# ConnectorBreakout.net
KiCad netlist of a schematic drawn in Altium Designer
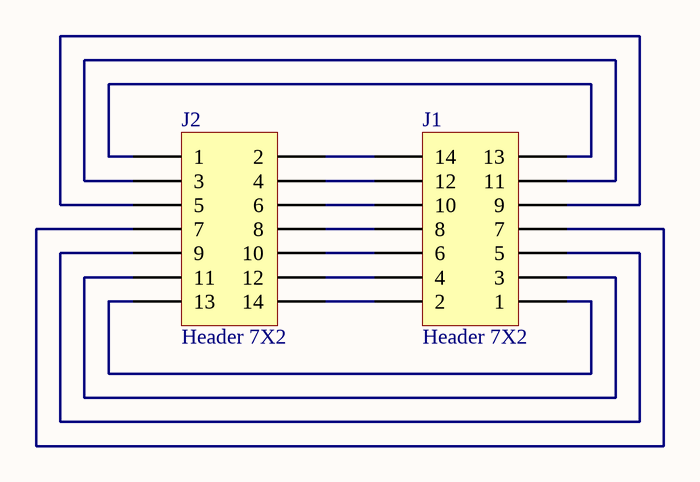
[diagram p0: ConnectorBreakout.SchDoc]

(export (version "E")
  (design (tool "Eeschema 10.0.6"))
  (components
    (comp (ref "J1")
      (value "Header 7X2")
      (footprint "HDR2X7H")
      (description "Header, 7-Pin, Dual row")
      (fields (field (name "PUBLISHER") "Altium Limited"))
      (libsource (lib "") (part "Header 7X2_1"))
    )
    (comp (ref "J2")
      (value "Header 7X2")
      (footprint "CLP-107-02-L-DH-TR")
      (description "Header, 7-Pin, Dual row")
      (fields (field (name "PUBLISHER") "Altium Limited"))
      (libsource (lib "Miscellaneous Connectors") (part "Header 7X2"))
    )
  )
  (nets
    (net (code "1") (name "Net-(J1-Pad1)") (class "Default")
      (node (ref "J1") (pin "1") (pinfunction "1_1") (pintype "passive"))
      (node (ref "J2") (pin "13") (pinfunction "13_13") (pintype "passive"))
    )
    (net (code "2") (name "Net-(J1-Pad2)") (class "Default")
      (node (ref "J1") (pin "2") (pinfunction "2_2") (pintype "passive"))
      (node (ref "J2") (pin "14") (pinfunction "14_14") (pintype "passive"))
    )
    (net (code "3") (name "Net-(J1-Pad3)") (class "Default")
      (node (ref "J1") (pin "3") (pinfunction "3_3") (pintype "passive"))
      (node (ref "J2") (pin "11") (pinfunction "11_11") (pintype "passive"))
    )
    (net (code "4") (name "Net-(J1-Pad4)") (class "Default")
      (node (ref "J1") (pin "4") (pinfunction "4_4") (pintype "passive"))
      (node (ref "J2") (pin "12") (pinfunction "12_12") (pintype "passive"))
    )
    (net (code "5") (name "Net-(J1-Pad5)") (class "Default")
      (node (ref "J1") (pin "5") (pinfunction "5_5") (pintype "passive"))
      (node (ref "J2") (pin "9") (pinfunction "9_9") (pintype "passive"))
    )
    (net (code "6") (name "Net-(J1-Pad6)") (class "Default")
      (node (ref "J1") (pin "6") (pinfunction "6_6") (pintype "passive"))
      (node (ref "J2") (pin "10") (pinfunction "10_10") (pintype "passive"))
    )
    (net (code "7") (name "Net-(J1-Pad7)") (class "Default")
      (node (ref "J1") (pin "7") (pinfunction "7_7") (pintype "passive"))
      (node (ref "J2") (pin "7") (pinfunction "7_7") (pintype "passive"))
    )
    (net (code "8") (name "Net-(J1-Pad8)") (class "Default")
      (node (ref "J1") (pin "8") (pinfunction "8_8") (pintype "passive"))
      (node (ref "J2") (pin "8") (pinfunction "8_8") (pintype "passive"))
    )
    (net (code "9") (name "Net-(J1-Pad9)") (class "Default")
      (node (ref "J1") (pin "9") (pinfunction "9_9") (pintype "passive"))
      (node (ref "J2") (pin "5") (pinfunction "5_5") (pintype "passive"))
    )
    (net (code "10") (name "Net-(J1-Pad10)") (class "Default")
      (node (ref "J1") (pin "10") (pinfunction "10_10") (pintype "passive"))
      (node (ref "J2") (pin "6") (pinfunction "6_6") (pintype "passive"))
    )
    (net (code "11") (name "Net-(J1-Pad11)") (class "Default")
      (node (ref "J1") (pin "11") (pinfunction "11_11") (pintype "passive"))
      (node (ref "J2") (pin "3") (pinfunction "3_3") (pintype "passive"))
    )
    (net (code "12") (name "Net-(J1-Pad12)") (class "Default")
      (node (ref "J1") (pin "12") (pinfunction "12_12") (pintype "passive"))
      (node (ref "J2") (pin "4") (pinfunction "4_4") (pintype "passive"))
    )
    (net (code "13") (name "Net-(J1-Pad13)") (class "Default")
      (node (ref "J1") (pin "13") (pinfunction "13_13") (pintype "passive"))
      (node (ref "J2") (pin "1") (pinfunction "1_1") (pintype "passive"))
    )
    (net (code "14") (name "Net-(J1-Pad14)") (class "Default")
      (node (ref "J1") (pin "14") (pinfunction "14_14") (pintype "passive"))
      (node (ref "J2") (pin "2") (pinfunction "2_2") (pintype "passive"))
    )
  )
)
